# Sheet1.net
KiCad netlist of a schematic drawn in Altium Designer
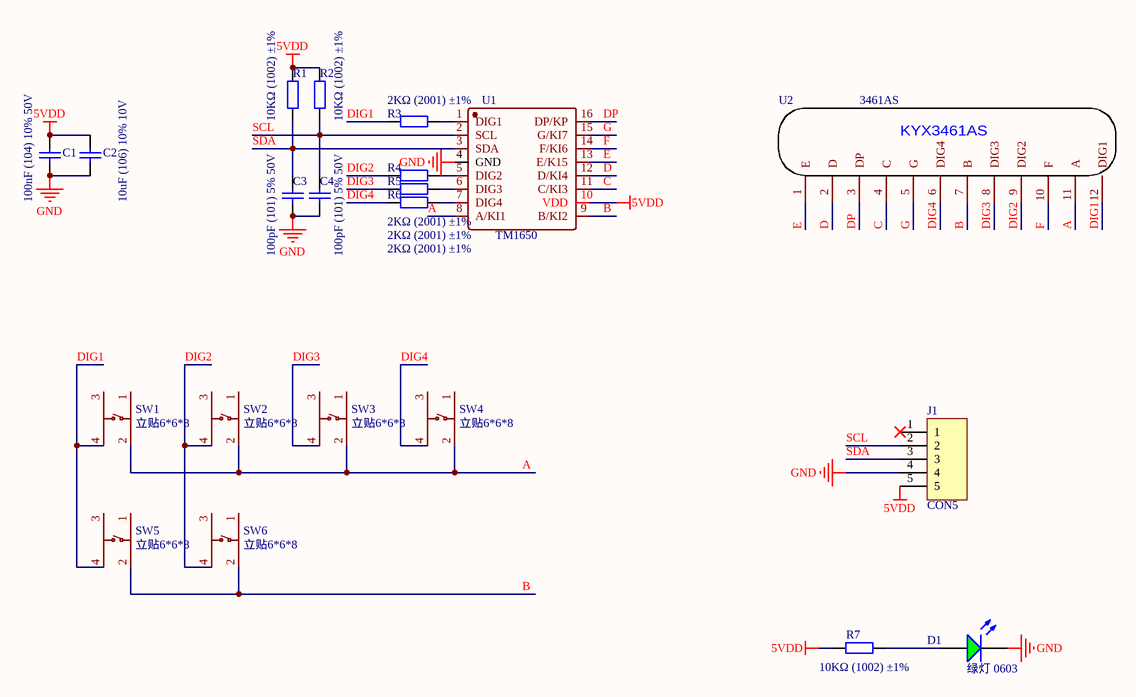
[diagram p0: Sheet1.SchDoc]

(export (version "E")
  (design (tool "Eeschema 10.0.6"))
  (components
    (comp (ref "C1")
      (value "100nF (104) 10% 50V")
      (footprint "0603_C")
      (description "贴片电容")
      (libsource (lib "Miscellaneous Devices LC") (part "0603 100nF (104) 10% 50V"))
    )
    (comp (ref "C2")
      (value "10uF (106) 10% 10V")
      (footprint "0603_C")
      (description "贴片电容")
      (libsource (lib "Miscellaneous Devices LC") (part "0603 10uF (106) 10% 10V"))
    )
    (comp (ref "C3")
      (value "100pF (101) 5% 50V")
      (footprint "0603_C")
      (description "贴片电容")
      (libsource (lib "Miscellaneous Devices LC") (part "0603 100pF (101) 5% 50V"))
    )
    (comp (ref "C4")
      (value "100pF (101) 5% 50V")
      (footprint "0603_C")
      (description "贴片电容")
      (libsource (lib "Miscellaneous Devices LC") (part "0603 100pF (101) 5% 50V"))
    )
    (comp (ref "D1")
      (value "绿灯 0603")
      (footprint "0603_LED_S1")
      (description "发光二极管")
      (libsource (lib "Miscellaneous Devices LC") (part "0603 绿灯"))
    )
    (comp (ref "J1") (value "CON5") (footprint "XH2.54-5P") (libsource (lib "RayPCB20210502") (part "CON5")))
    (comp (ref "R1")
      (value "10KΩ (1002) ±1%")
      (footprint "0603_R")
      (description "贴片电阻")
      (libsource (lib "Miscellaneous Devices LC") (part "0603 10KΩ (1002) 1%"))
    )
    (comp (ref "R2")
      (value "10KΩ (1002) ±1%")
      (footprint "0603_R")
      (description "贴片电阻")
      (libsource (lib "Miscellaneous Devices LC") (part "0603 10KΩ (1002) 1%"))
    )
    (comp (ref "R3")
      (value "2KΩ (2001) ±1%")
      (footprint "0603_R")
      (description "贴片电阻")
      (libsource (lib "Miscellaneous Devices LC") (part "0603 2KΩ (2001) 1%"))
    )
    (comp (ref "R4")
      (value "2KΩ (2001) ±1%")
      (footprint "0603_R")
      (description "贴片电阻")
      (libsource (lib "Miscellaneous Devices LC") (part "0603 2KΩ (2001) 1%"))
    )
    (comp (ref "R5")
      (value "2KΩ (2001) ±1%")
      (footprint "0603_R")
      (description "贴片电阻")
      (libsource (lib "Miscellaneous Devices LC") (part "0603 2KΩ (2001) 1%"))
    )
    (comp (ref "R6")
      (value "2KΩ (2001) ±1%")
      (footprint "0603_R")
      (description "贴片电阻")
      (libsource (lib "Miscellaneous Devices LC") (part "0603 2KΩ (2001) 1%"))
    )
    (comp (ref "R7")
      (value "10KΩ (1002) ±1%")
      (footprint "0603_R")
      (description "贴片电阻")
      (libsource (lib "") (part "0603 10KΩ (1002) 1%_1"))
    )
    (comp (ref "SW1") (value "立贴6*6*8") (footprint "SW") (libsource (lib "RayPCB20210502") (part "SW")))
    (comp (ref "SW2") (value "立贴6*6*8") (footprint "SW") (libsource (lib "RayPCB20210502") (part "SW")))
    (comp (ref "SW3") (value "立贴6*6*8") (footprint "SW") (libsource (lib "RayPCB20210502") (part "SW")))
    (comp (ref "SW4") (value "立贴6*6*8") (footprint "SW") (libsource (lib "RayPCB20210502") (part "SW")))
    (comp (ref "SW5") (value "立贴6*6*8") (footprint "SW") (libsource (lib "RayPCB20210502") (part "SW")))
    (comp (ref "SW6") (value "立贴6*6*8") (footprint "SW") (libsource (lib "RayPCB20210502") (part "SW")))
    (comp (ref "U1") (value "TM1650") (footprint "TM1650") (libsource (lib "RayPCB20210502") (part "TM1650")))
    (comp (ref "U2") (value "3461AS") (footprint "3461AS") (libsource (lib "RayPCB20210502") (part "3461AS")))
  )
  (nets
    (net (code "1") (name "/A") (class "Default")
      (node (ref "SW1") (pin "2") (pinfunction "2_2") (pintype "passive"))
      (node (ref "SW2") (pin "2") (pinfunction "2_2") (pintype "passive"))
      (node (ref "SW3") (pin "2") (pinfunction "2_2") (pintype "passive"))
      (node (ref "SW4") (pin "2") (pinfunction "2_2") (pintype "passive"))
      (node (ref "U1") (pin "8") (pinfunction "A/KI1_8") (pintype "passive"))
      (node (ref "U2") (pin "11") (pinfunction "A_11") (pintype "passive"))
    )
    (net (code "2") (name "/B") (class "Default")
      (node (ref "SW5") (pin "2") (pinfunction "2_2") (pintype "passive"))
      (node (ref "SW6") (pin "2") (pinfunction "2_2") (pintype "passive"))
      (node (ref "U1") (pin "9") (pinfunction "B/KI2_9") (pintype "passive"))
      (node (ref "U2") (pin "7") (pinfunction "B_7") (pintype "passive"))
    )
    (net (code "3") (name "/C") (class "Default")
      (node (ref "U1") (pin "11") (pinfunction "C/KI3_11") (pintype "passive"))
      (node (ref "U2") (pin "4") (pinfunction "C_4") (pintype "passive"))
    )
    (net (code "4") (name "/D") (class "Default")
      (node (ref "U1") (pin "12") (pinfunction "D/KI4_12") (pintype "passive"))
      (node (ref "U2") (pin "2") (pinfunction "D_2") (pintype "passive"))
    )
    (net (code "5") (name "/DIG1") (class "Default")
      (node (ref "R3") (pin "1") (pinfunction "1_1") (pintype "passive"))
      (node (ref "SW1") (pin "4") (pinfunction "4_4") (pintype "passive"))
      (node (ref "SW5") (pin "4") (pinfunction "4_4") (pintype "passive"))
      (node (ref "U2") (pin "12") (pinfunction "DIG1_12") (pintype "passive"))
    )
    (net (code "6") (name "/DIG2") (class "Default")
      (node (ref "R4") (pin "1") (pinfunction "1_1") (pintype "passive"))
      (node (ref "SW2") (pin "4") (pinfunction "4_4") (pintype "passive"))
      (node (ref "SW6") (pin "4") (pinfunction "4_4") (pintype "passive"))
      (node (ref "U2") (pin "9") (pinfunction "DIG2_9") (pintype "passive"))
    )
    (net (code "7") (name "/DIG3") (class "Default")
      (node (ref "R5") (pin "1") (pinfunction "1_1") (pintype "passive"))
      (node (ref "SW3") (pin "4") (pinfunction "4_4") (pintype "passive"))
      (node (ref "U2") (pin "8") (pinfunction "DIG3_8") (pintype "passive"))
    )
    (net (code "8") (name "/DIG4") (class "Default")
      (node (ref "R6") (pin "1") (pinfunction "1_1") (pintype "passive"))
      (node (ref "SW4") (pin "4") (pinfunction "4_4") (pintype "passive"))
      (node (ref "U2") (pin "6") (pinfunction "DIG4_6") (pintype "passive"))
    )
    (net (code "9") (name "/DP") (class "Default")
      (node (ref "U1") (pin "16") (pinfunction "DP/KP_16") (pintype "passive"))
      (node (ref "U2") (pin "3") (pinfunction "DP_3") (pintype "passive"))
    )
    (net (code "10") (name "/E") (class "Default")
      (node (ref "U1") (pin "13") (pinfunction "E/K15_13") (pintype "passive"))
      (node (ref "U2") (pin "1") (pinfunction "E_1") (pintype "passive"))
    )
    (net (code "11") (name "/F") (class "Default")
      (node (ref "U1") (pin "14") (pinfunction "F/KI6_14") (pintype "passive"))
      (node (ref "U2") (pin "10") (pinfunction "F_10") (pintype "passive"))
    )
    (net (code "12") (name "/G") (class "Default")
      (node (ref "U1") (pin "15") (pinfunction "G/KI7_15") (pintype "passive"))
      (node (ref "U2") (pin "5") (pinfunction "G_5") (pintype "passive"))
    )
    (net (code "13") (name "/SCL") (class "Default")
      (node (ref "C4") (pin "2") (pinfunction "2_2") (pintype "passive"))
      (node (ref "J1") (pin "2") (pinfunction "2_2") (pintype "passive"))
      (node (ref "R2") (pin "1") (pinfunction "1_1") (pintype "passive"))
      (node (ref "U1") (pin "2") (pinfunction "SCL_2") (pintype "passive"))
    )
    (net (code "14") (name "/SDA") (class "Default")
      (node (ref "C3") (pin "2") (pinfunction "2_2") (pintype "passive"))
      (node (ref "J1") (pin "3") (pinfunction "3_3") (pintype "passive"))
      (node (ref "R1") (pin "1") (pinfunction "1_1") (pintype "passive"))
      (node (ref "U1") (pin "3") (pinfunction "SDA_3") (pintype "passive"))
    )
    (net (code "15") (name "5VDD") (class "Default")
      (node (ref "C1") (pin "2") (pinfunction "2_2") (pintype "passive"))
      (node (ref "C2") (pin "2") (pinfunction "2_2") (pintype "passive"))
      (node (ref "J1") (pin "5") (pinfunction "5_5") (pintype "passive"))
      (node (ref "R1") (pin "2") (pinfunction "2_2") (pintype "passive"))
      (node (ref "R2") (pin "2") (pinfunction "2_2") (pintype "passive"))
      (node (ref "R7") (pin "1") (pinfunction "1_1") (pintype "passive"))
      (node (ref "U1") (pin "10") (pinfunction "VDD_10") (pintype "passive"))
    )
    (net (code "16") (name "GND") (class "Default")
      (node (ref "C1") (pin "1") (pinfunction "1_1") (pintype "passive"))
      (node (ref "C2") (pin "1") (pinfunction "1_1") (pintype "passive"))
      (node (ref "C3") (pin "1") (pinfunction "1_1") (pintype "passive"))
      (node (ref "C4") (pin "1") (pinfunction "1_1") (pintype "passive"))
      (node (ref "D1") (pin "K") (pinfunction "K_K") (pintype "passive"))
      (node (ref "J1") (pin "4") (pinfunction "4_4") (pintype "passive"))
      (node (ref "U1") (pin "4") (pinfunction "GND_4") (pintype "passive"))
    )
    (net (code "17") (name "Net-(D1-PadA)") (class "Default")
      (node (ref "D1") (pin "A") (pinfunction "A_A") (pintype "passive"))
      (node (ref "R7") (pin "2") (pinfunction "2_2") (pintype "passive"))
    )
    (net (code "18") (name "Net-(U1-DIG1)") (class "Default")
      (node (ref "R3") (pin "2") (pinfunction "2_2") (pintype "passive"))
      (node (ref "U1") (pin "1") (pinfunction "DIG1_1") (pintype "passive"))
    )
    (net (code "19") (name "Net-(U1-DIG2)") (class "Default")
      (node (ref "R4") (pin "2") (pinfunction "2_2") (pintype "passive"))
      (node (ref "U1") (pin "5") (pinfunction "DIG2_5") (pintype "passive"))
    )
    (net (code "20") (name "Net-(U1-DIG3)") (class "Default")
      (node (ref "R5") (pin "2") (pinfunction "2_2") (pintype "passive"))
      (node (ref "U1") (pin "6") (pinfunction "DIG3_6") (pintype "passive"))
    )
    (net (code "21") (name "Net-(U1-DIG4)") (class "Default")
      (node (ref "R6") (pin "2") (pinfunction "2_2") (pintype "passive"))
      (node (ref "U1") (pin "7") (pinfunction "DIG4_7") (pintype "passive"))
    )
    (net (code "22") (name "unconnected-(J1-Pad1)") (class "Default")
      (node (ref "J1") (pin "1") (pinfunction "1_1") (pintype "passive+no_connect"))
    )
    (net (code "23") (name "unconnected-(SW1-Pad1)") (class "Default")
      (node (ref "SW1") (pin "1") (pinfunction "1_1") (pintype "passive"))
    )
    (net (code "24") (name "unconnected-(SW1-Pad3)") (class "Default")
      (node (ref "SW1") (pin "3") (pinfunction "3_3") (pintype "passive"))
    )
    (net (code "25") (name "unconnected-(SW2-Pad1)") (class "Default")
      (node (ref "SW2") (pin "1") (pinfunction "1_1") (pintype "passive"))
    )
    (net (code "26") (name "unconnected-(SW2-Pad3)") (class "Default")
      (node (ref "SW2") (pin "3") (pinfunction "3_3") (pintype "passive"))
    )
    (net (code "27") (name "unconnected-(SW3-Pad1)") (class "Default")
      (node (ref "SW3") (pin "1") (pinfunction "1_1") (pintype "passive"))
    )
    (net (code "28") (name "unconnected-(SW3-Pad3)") (class "Default")
      (node (ref "SW3") (pin "3") (pinfunction "3_3") (pintype "passive"))
    )
    (net (code "29") (name "unconnected-(SW4-Pad1)") (class "Default")
      (node (ref "SW4") (pin "1") (pinfunction "1_1") (pintype "passive"))
    )
    (net (code "30") (name "unconnected-(SW4-Pad3)") (class "Default")
      (node (ref "SW4") (pin "3") (pinfunction "3_3") (pintype "passive"))
    )
    (net (code "31") (name "unconnected-(SW5-Pad1)") (class "Default")
      (node (ref "SW5") (pin "1") (pinfunction "1_1") (pintype "passive"))
    )
    (net (code "32") (name "unconnected-(SW5-Pad3)") (class "Default")
      (node (ref "SW5") (pin "3") (pinfunction "3_3") (pintype "passive"))
    )
    (net (code "33") (name "unconnected-(SW6-Pad1)") (class "Default")
      (node (ref "SW6") (pin "1") (pinfunction "1_1") (pintype "passive"))
    )
    (net (code "34") (name "unconnected-(SW6-Pad3)") (class "Default")
      (node (ref "SW6") (pin "3") (pinfunction "3_3") (pintype "passive"))
    )
  )
)
